# PX4FMUv2_4_6_1.net
KiCad netlist of a schematic drawn in Altium Designer
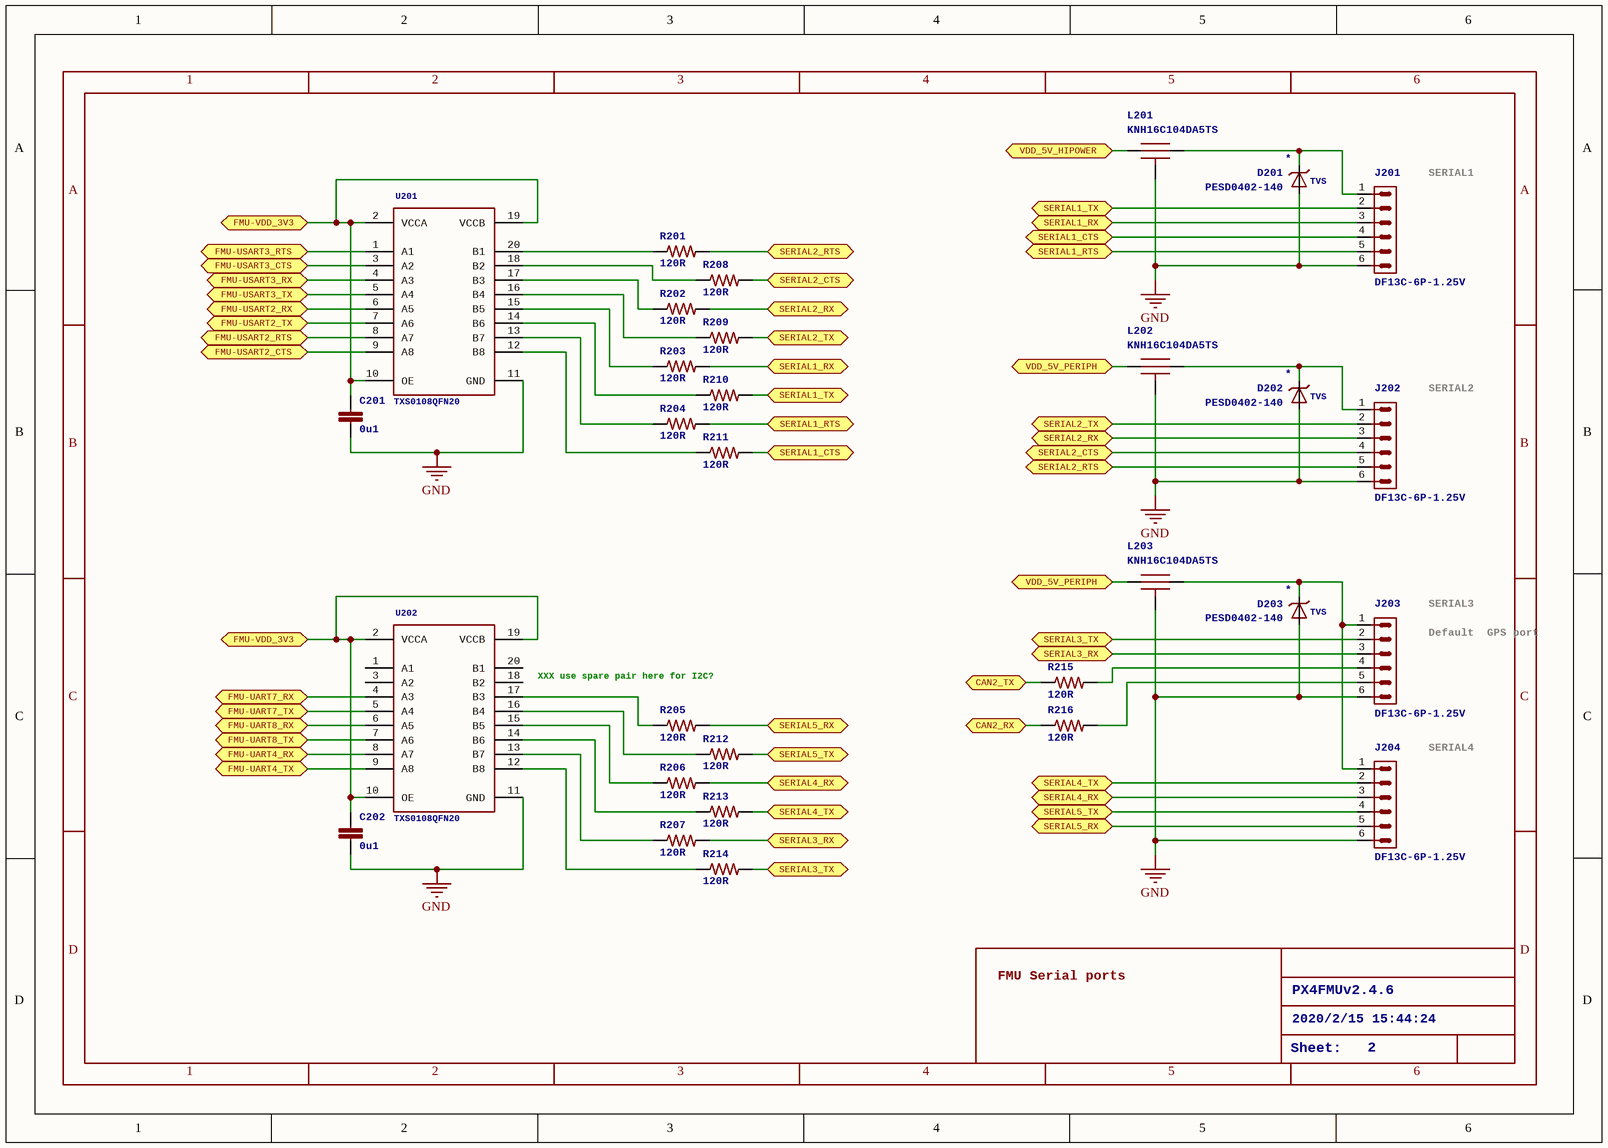
[diagram p0: PX4FMUv2.4.6_1.SchDoc]

(export (version "E")
  (design (tool "Eeschema 10.0.6"))
  (components
    (comp (ref "C201")
      (value "0u1")
      (footprint "0402-CAP")
      (description "CapacitorStandard 0603 ceramic capacitor, and 0.1\" leaded capacitor.")
      (fields (field (name "PARTNO") "CC0402ZRY5V7BB104"))
      (libsource (lib "pixhawk2") (part "CAP0402"))
    )
    (comp (ref "C202")
      (value "0u1")
      (footprint "0402-CAP")
      (description "CapacitorStandard 0603 ceramic capacitor, and 0.1\" leaded capacitor.")
      (fields (field (name "PARTNO") "CC0402ZRY5V7BB104"))
      (libsource (lib "pixhawk2") (part "CAP0402"))
    )
    (comp (ref "D201")
      (value "PESD0402-140")
      (footprint "0402-TVS")
      (fields (field (name "NAME") "*") (field (name "TVS") "TVS"))
      (libsource (lib "pixhawk2") (part "DIODE-TVS"))
    )
    (comp (ref "D202")
      (value "PESD0402-140")
      (footprint "0402-TVS")
      (fields (field (name "NAME") "*") (field (name "TVS") "TVS"))
      (libsource (lib "pixhawk2") (part "DIODE-TVS"))
    )
    (comp (ref "D203")
      (value "PESD0402-140")
      (footprint "0402-TVS")
      (fields (field (name "NAME") "*") (field (name "TVS") "TVS"))
      (libsource (lib "pixhawk2") (part "DIODE-TVS"))
    )
    (comp (ref "J201")
      (value "DF13C-6P-1.25V")
      (footprint "DF13C-6P-1.25V")
      (description "DF13-6P 1.25mm Pitch Miniature Crimping Connector.")
      (fields (field (name "PARTNO") "DF13C-6P-1.25V(20)") (field (name "LIBRARYNAME") "con-hirose-df13"))
      (libsource (lib "con-hirose-df13") (part "DF13-6P-1.25V"))
    )
    (comp (ref "J202")
      (value "DF13C-6P-1.25V")
      (footprint "DF13C-6P-1.25V")
      (description "DF13-6P 1.25mm Pitch Miniature Crimping Connector.")
      (fields (field (name "PARTNO") "DF13C-6P-1.25V(20)") (field (name "LIBRARYNAME") "con-hirose-df13"))
      (libsource (lib "con-hirose-df13") (part "DF13-6P-1.25V"))
    )
    (comp (ref "J203")
      (value "DF13C-6P-1.25V")
      (footprint "DF13C-6P-1.25V")
      (description "DF13-6P 1.25mm Pitch Miniature Crimping Connector.")
      (fields (field (name "PARTNO") "DF13C-6P-1.25V(20)") (field (name "LIBRARYNAME") "con-hirose-df13"))
      (libsource (lib "con-hirose-df13") (part "DF13-6P-1.25V"))
    )
    (comp (ref "J204")
      (value "DF13C-6P-1.25V")
      (footprint "DF13C-6P-1.25V")
      (description "DF13-6P 1.25mm Pitch Miniature Crimping Connector.")
      (fields (field (name "PARTNO") "DF13C-6P-1.25V(20)") (field (name "LIBRARYNAME") "con-hirose-df13"))
      (libsource (lib "con-hirose-df13") (part "DF13-6P-1.25V"))
    )
    (comp (ref "L201")
      (value "KNH16C104DA5TS")
      (footprint "KYOCERA-KNH16-DA")
      (description "Kyocera KNH16C104DA5TS EMI filter")
      (libsource (lib "pixhawk2") (part "KNH16C104DA5TS"))
    )
    (comp (ref "L202")
      (value "KNH16C104DA5TS")
      (footprint "KYOCERA-KNH16-DA")
      (description "Kyocera KNH16C104DA5TS EMI filter")
      (libsource (lib "pixhawk2") (part "KNH16C104DA5TS"))
    )
    (comp (ref "L203")
      (value "KNH16C104DA5TS")
      (footprint "KYOCERA-KNH16-DA")
      (description "Kyocera KNH16C104DA5TS EMI filter")
      (libsource (lib "pixhawk2") (part "KNH16C104DA5TS"))
    )
    (comp (ref "R201")
      (value "120R")
      (footprint "0402-RES")
      (fields (field (name "PARTNO") "RC0402FR-07120RL"))
      (libsource (lib "pixhawk2") (part "RESISTOR0402-RES"))
    )
    (comp (ref "R202")
      (value "120R")
      (footprint "0402-RES")
      (fields (field (name "PARTNO") "RC0402FR-07120RL"))
      (libsource (lib "pixhawk2") (part "RESISTOR0402-RES"))
    )
    (comp (ref "R203")
      (value "120R")
      (footprint "0402-RES")
      (fields (field (name "PARTNO") "RC0402FR-07120RL"))
      (libsource (lib "pixhawk2") (part "RESISTOR0402-RES"))
    )
    (comp (ref "R204")
      (value "120R")
      (footprint "0402-RES")
      (fields (field (name "PARTNO") "RC0402FR-07120RL"))
      (libsource (lib "pixhawk2") (part "RESISTOR0402-RES"))
    )
    (comp (ref "R205")
      (value "120R")
      (footprint "0402-RES")
      (fields (field (name "PARTNO") "RC0402FR-07120RL"))
      (libsource (lib "pixhawk2") (part "RESISTOR0402-RES"))
    )
    (comp (ref "R206")
      (value "120R")
      (footprint "0402-RES")
      (fields (field (name "PARTNO") "RC0402FR-07120RL"))
      (libsource (lib "pixhawk2") (part "RESISTOR0402-RES"))
    )
    (comp (ref "R207")
      (value "120R")
      (footprint "0402-RES")
      (fields (field (name "PARTNO") "RC0402FR-07120RL"))
      (libsource (lib "pixhawk2") (part "RESISTOR0402-RES"))
    )
    (comp (ref "R208")
      (value "120R")
      (footprint "0402-RES")
      (fields (field (name "PARTNO") "RC0402FR-07120RL"))
      (libsource (lib "pixhawk2") (part "RESISTOR0402-RES"))
    )
    (comp (ref "R209")
      (value "120R")
      (footprint "0402-RES")
      (fields (field (name "PARTNO") "RC0402FR-07120RL"))
      (libsource (lib "pixhawk2") (part "RESISTOR0402-RES"))
    )
    (comp (ref "R210")
      (value "120R")
      (footprint "0402-RES")
      (fields (field (name "PARTNO") "RC0402FR-07120RL"))
      (libsource (lib "pixhawk2") (part "RESISTOR0402-RES"))
    )
    (comp (ref "R211")
      (value "120R")
      (footprint "0402-RES")
      (fields (field (name "PARTNO") "RC0402FR-07120RL"))
      (libsource (lib "pixhawk2") (part "RESISTOR0402-RES"))
    )
    (comp (ref "R212")
      (value "120R")
      (footprint "0402-RES")
      (fields (field (name "PARTNO") "RC0402FR-07120RL"))
      (libsource (lib "pixhawk2") (part "RESISTOR0402-RES"))
    )
    (comp (ref "R213")
      (value "120R")
      (footprint "0402-RES")
      (fields (field (name "PARTNO") "RC0402FR-07120RL"))
      (libsource (lib "pixhawk2") (part "RESISTOR0402-RES"))
    )
    (comp (ref "R214")
      (value "120R")
      (footprint "0402-RES")
      (fields (field (name "PARTNO") "RC0402FR-07120RL"))
      (libsource (lib "pixhawk2") (part "RESISTOR0402-RES"))
    )
    (comp (ref "R215")
      (value "120R")
      (footprint "0402-RES")
      (fields (field (name "PARTNO") "RC0402FR-07120RL"))
      (libsource (lib "pixhawk2") (part "RESISTOR0402-RES"))
    )
    (comp (ref "R216")
      (value "120R")
      (footprint "0402-RES")
      (fields (field (name "PARTNO") "RC0402FR-07120RL"))
      (libsource (lib "pixhawk2") (part "RESISTOR0402-RES"))
    )
    (comp (ref "U201")
      (value "TXS0108QFN20")
      (footprint "QFN20-RGY")
      (fields (field (name "PARTNO") "TXS0108ERGYR"))
      (libsource (lib "pixhawk2") (part "TXS0108QFN20"))
    )
    (comp (ref "U202")
      (value "TXS0108QFN20")
      (footprint "QFN20-RGY")
      (fields (field (name "PARTNO") "TXS0108ERGYR"))
      (libsource (lib "pixhawk2") (part "TXS0108QFN20"))
    )
  )
  (nets
    (net (code "1") (name "/CAN2_RX") (class "Default")
      (node (ref "R216") (pin "P$1") (pinfunction "1_P$1") (pintype "passive"))
    )
    (net (code "2") (name "/CAN2_TX") (class "Default")
      (node (ref "R215") (pin "P$1") (pinfunction "1_P$1") (pintype "passive"))
    )
    (net (code "3") (name "/FMU-UART4_RX") (class "Default")
      (node (ref "U202") (pin "8") (pinfunction "A7_8") (pintype "passive"))
    )
    (net (code "4") (name "/FMU-UART4_TX") (class "Default")
      (node (ref "U202") (pin "9") (pinfunction "A8_9") (pintype "passive"))
    )
    (net (code "5") (name "/FMU-UART7_RX") (class "Default")
      (node (ref "U202") (pin "4") (pinfunction "A3_4") (pintype "passive"))
    )
    (net (code "6") (name "/FMU-UART7_TX") (class "Default")
      (node (ref "U202") (pin "5") (pinfunction "A4_5") (pintype "passive"))
    )
    (net (code "7") (name "/FMU-UART8_RX") (class "Default")
      (node (ref "U202") (pin "6") (pinfunction "A5_6") (pintype "passive"))
    )
    (net (code "8") (name "/FMU-UART8_TX") (class "Default")
      (node (ref "U202") (pin "7") (pinfunction "A6_7") (pintype "passive"))
    )
    (net (code "9") (name "/FMU-USART2_CTS") (class "Default")
      (node (ref "U201") (pin "9") (pinfunction "A8_9") (pintype "passive"))
    )
    (net (code "10") (name "/FMU-USART2_RTS") (class "Default")
      (node (ref "U201") (pin "8") (pinfunction "A7_8") (pintype "passive"))
    )
    (net (code "11") (name "/FMU-USART2_RX") (class "Default")
      (node (ref "U201") (pin "6") (pinfunction "A5_6") (pintype "passive"))
    )
    (net (code "12") (name "/FMU-USART2_TX") (class "Default")
      (node (ref "U201") (pin "7") (pinfunction "A6_7") (pintype "passive"))
    )
    (net (code "13") (name "/FMU-USART3_CTS") (class "Default")
      (node (ref "U201") (pin "3") (pinfunction "A2_3") (pintype "passive"))
    )
    (net (code "14") (name "/FMU-USART3_RTS") (class "Default")
      (node (ref "U201") (pin "1") (pinfunction "A1_1") (pintype "passive"))
    )
    (net (code "15") (name "/FMU-USART3_RX") (class "Default")
      (node (ref "U201") (pin "4") (pinfunction "A3_4") (pintype "passive"))
    )
    (net (code "16") (name "/FMU-USART3_TX") (class "Default")
      (node (ref "U201") (pin "5") (pinfunction "A4_5") (pintype "passive"))
    )
    (net (code "17") (name "/FMU-VDD_3V3") (class "Default")
      (node (ref "C201") (pin "P$1") (pinfunction "1_P$1") (pintype "passive"))
      (node (ref "C202") (pin "P$1") (pinfunction "1_P$1") (pintype "passive"))
      (node (ref "U201") (pin "10") (pinfunction "OE_10") (pintype "passive"))
      (node (ref "U201") (pin "19") (pinfunction "VCCB_19") (pintype "passive"))
      (node (ref "U201") (pin "2") (pinfunction "VCCA_2") (pintype "passive"))
      (node (ref "U202") (pin "10") (pinfunction "OE_10") (pintype "passive"))
      (node (ref "U202") (pin "19") (pinfunction "VCCB_19") (pintype "passive"))
      (node (ref "U202") (pin "2") (pinfunction "VCCA_2") (pintype "passive"))
    )
    (net (code "18") (name "/SERIAL1_CTS") (class "Default")
      (node (ref "J201") (pin "4") (pinfunction "4_4") (pintype "passive"))
      (node (ref "R211") (pin "P$2") (pinfunction "2_P$2") (pintype "passive"))
    )
    (net (code "19") (name "/SERIAL1_RTS") (class "Default")
      (node (ref "J201") (pin "5") (pinfunction "5_5") (pintype "passive"))
      (node (ref "R204") (pin "P$2") (pinfunction "2_P$2") (pintype "passive"))
    )
    (net (code "20") (name "/SERIAL1_RX") (class "Default")
      (node (ref "J201") (pin "3") (pinfunction "3_3") (pintype "passive"))
      (node (ref "R203") (pin "P$2") (pinfunction "2_P$2") (pintype "passive"))
    )
    (net (code "21") (name "/SERIAL1_TX") (class "Default")
      (node (ref "J201") (pin "2") (pinfunction "2_2") (pintype "passive"))
      (node (ref "R210") (pin "P$2") (pinfunction "2_P$2") (pintype "passive"))
    )
    (net (code "22") (name "/SERIAL2_CTS") (class "Default")
      (node (ref "J202") (pin "4") (pinfunction "4_4") (pintype "passive"))
      (node (ref "R208") (pin "P$2") (pinfunction "2_P$2") (pintype "passive"))
    )
    (net (code "23") (name "/SERIAL2_RTS") (class "Default")
      (node (ref "J202") (pin "5") (pinfunction "5_5") (pintype "passive"))
      (node (ref "R201") (pin "P$2") (pinfunction "2_P$2") (pintype "passive"))
    )
    (net (code "24") (name "/SERIAL2_RX") (class "Default")
      (node (ref "J202") (pin "3") (pinfunction "3_3") (pintype "passive"))
      (node (ref "R202") (pin "P$2") (pinfunction "2_P$2") (pintype "passive"))
    )
    (net (code "25") (name "/SERIAL2_TX") (class "Default")
      (node (ref "J202") (pin "2") (pinfunction "2_2") (pintype "passive"))
      (node (ref "R209") (pin "P$2") (pinfunction "2_P$2") (pintype "passive"))
    )
    (net (code "26") (name "/SERIAL3_RX") (class "Default")
      (node (ref "J203") (pin "3") (pinfunction "3_3") (pintype "passive"))
      (node (ref "R207") (pin "P$2") (pinfunction "2_P$2") (pintype "passive"))
    )
    (net (code "27") (name "/SERIAL3_TX") (class "Default")
      (node (ref "J203") (pin "2") (pinfunction "2_2") (pintype "passive"))
      (node (ref "R214") (pin "P$2") (pinfunction "2_P$2") (pintype "passive"))
    )
    (net (code "28") (name "/SERIAL4_RX") (class "Default")
      (node (ref "J204") (pin "3") (pinfunction "3_3") (pintype "passive"))
      (node (ref "R206") (pin "P$2") (pinfunction "2_P$2") (pintype "passive"))
    )
    (net (code "29") (name "/SERIAL4_TX") (class "Default")
      (node (ref "J204") (pin "2") (pinfunction "2_2") (pintype "passive"))
      (node (ref "R213") (pin "P$2") (pinfunction "2_P$2") (pintype "passive"))
    )
    (net (code "30") (name "/SERIAL5_RX") (class "Default")
      (node (ref "J204") (pin "5") (pinfunction "5_5") (pintype "passive"))
      (node (ref "R205") (pin "P$2") (pinfunction "2_P$2") (pintype "passive"))
    )
    (net (code "31") (name "/SERIAL5_TX") (class "Default")
      (node (ref "J204") (pin "4") (pinfunction "4_4") (pintype "passive"))
      (node (ref "R212") (pin "P$2") (pinfunction "2_P$2") (pintype "passive"))
    )
    (net (code "32") (name "/VDD_5V_HIPOWER") (class "Default")
      (node (ref "L201") (pin "P$1") (pinfunction "P$1_P$1") (pintype "passive"))
    )
    (net (code "33") (name "/VDD_5V_PERIPH") (class "Default")
      (node (ref "L202") (pin "P$1") (pinfunction "P$1_P$1") (pintype "passive"))
      (node (ref "L203") (pin "P$1") (pinfunction "P$1_P$1") (pintype "passive"))
    )
    (net (code "34") (name "GND") (class "Default")
      (node (ref "C201") (pin "P$2") (pinfunction "2_P$2") (pintype "passive"))
      (node (ref "C202") (pin "P$2") (pinfunction "2_P$2") (pintype "passive"))
      (node (ref "D201") (pin "A") (pinfunction "A_A") (pintype "passive"))
      (node (ref "D202") (pin "A") (pinfunction "A_A") (pintype "passive"))
      (node (ref "D203") (pin "A") (pinfunction "A_A") (pintype "passive"))
      (node (ref "J201") (pin "6") (pinfunction "6_6") (pintype "passive"))
      (node (ref "J202") (pin "6") (pinfunction "6_6") (pintype "passive"))
      (node (ref "J203") (pin "6") (pinfunction "6_6") (pintype "passive"))
      (node (ref "J204") (pin "6") (pinfunction "6_6") (pintype "passive"))
      (node (ref "L201") (pin "P$3_P$4_P$5") (pinfunction "P$3_P$3_P$4_P$5") (pintype "passive"))
      (node (ref "L202") (pin "P$3_P$4_P$5") (pinfunction "P$3_P$3_P$4_P$5") (pintype "passive"))
      (node (ref "L203") (pin "P$3_P$4_P$5") (pinfunction "P$3_P$3_P$4_P$5") (pintype "passive"))
      (node (ref "U201") (pin "11") (pinfunction "GND_11") (pintype "open_emitter"))
      (node (ref "U202") (pin "11") (pinfunction "GND_11") (pintype "open_emitter"))
    )
    (net (code "35") (name "Net-(D201-PadC)") (class "Default")
      (node (ref "D201") (pin "C") (pinfunction "C_C") (pintype "passive"))
      (node (ref "J201") (pin "1") (pinfunction "1_1") (pintype "passive"))
      (node (ref "L201") (pin "P$2") (pinfunction "P$2_P$2") (pintype "passive"))
    )
    (net (code "36") (name "Net-(D202-PadC)") (class "Default")
      (node (ref "D202") (pin "C") (pinfunction "C_C") (pintype "passive"))
      (node (ref "J202") (pin "1") (pinfunction "1_1") (pintype "passive"))
      (node (ref "L202") (pin "P$2") (pinfunction "P$2_P$2") (pintype "passive"))
    )
    (net (code "37") (name "Net-(D203-PadC)") (class "Default")
      (node (ref "D203") (pin "C") (pinfunction "C_C") (pintype "passive"))
      (node (ref "J203") (pin "1") (pinfunction "1_1") (pintype "passive"))
      (node (ref "J204") (pin "1") (pinfunction "1_1") (pintype "passive"))
      (node (ref "L203") (pin "P$2") (pinfunction "P$2_P$2") (pintype "passive"))
    )
    (net (code "38") (name "Net-(R201-1)") (class "Default")
      (node (ref "R201") (pin "P$1") (pinfunction "1_P$1") (pintype "passive"))
      (node (ref "U201") (pin "20") (pinfunction "B1_20") (pintype "passive"))
    )
    (net (code "39") (name "Net-(R202-1)") (class "Default")
      (node (ref "R202") (pin "P$1") (pinfunction "1_P$1") (pintype "passive"))
      (node (ref "U201") (pin "17") (pinfunction "B3_17") (pintype "passive"))
    )
    (net (code "40") (name "Net-(R203-1)") (class "Default")
      (node (ref "R203") (pin "P$1") (pinfunction "1_P$1") (pintype "passive"))
      (node (ref "U201") (pin "15") (pinfunction "B5_15") (pintype "passive"))
    )
    (net (code "41") (name "Net-(R204-1)") (class "Default")
      (node (ref "R204") (pin "P$1") (pinfunction "1_P$1") (pintype "passive"))
      (node (ref "U201") (pin "13") (pinfunction "B7_13") (pintype "passive"))
    )
    (net (code "42") (name "Net-(R205-1)") (class "Default")
      (node (ref "R205") (pin "P$1") (pinfunction "1_P$1") (pintype "passive"))
      (node (ref "U202") (pin "17") (pinfunction "B3_17") (pintype "passive"))
    )
    (net (code "43") (name "Net-(R206-1)") (class "Default")
      (node (ref "R206") (pin "P$1") (pinfunction "1_P$1") (pintype "passive"))
      (node (ref "U202") (pin "15") (pinfunction "B5_15") (pintype "passive"))
    )
    (net (code "44") (name "Net-(R207-1)") (class "Default")
      (node (ref "R207") (pin "P$1") (pinfunction "1_P$1") (pintype "passive"))
      (node (ref "U202") (pin "13") (pinfunction "B7_13") (pintype "passive"))
    )
    (net (code "45") (name "Net-(R208-1)") (class "Default")
      (node (ref "R208") (pin "P$1") (pinfunction "1_P$1") (pintype "passive"))
      (node (ref "U201") (pin "18") (pinfunction "B2_18") (pintype "passive"))
    )
    (net (code "46") (name "Net-(R209-1)") (class "Default")
      (node (ref "R209") (pin "P$1") (pinfunction "1_P$1") (pintype "passive"))
      (node (ref "U201") (pin "16") (pinfunction "B4_16") (pintype "passive"))
    )
    (net (code "47") (name "Net-(R210-1)") (class "Default")
      (node (ref "R210") (pin "P$1") (pinfunction "1_P$1") (pintype "passive"))
      (node (ref "U201") (pin "14") (pinfunction "B6_14") (pintype "passive"))
    )
    (net (code "48") (name "Net-(R211-1)") (class "Default")
      (node (ref "R211") (pin "P$1") (pinfunction "1_P$1") (pintype "passive"))
      (node (ref "U201") (pin "12") (pinfunction "B8_12") (pintype "passive"))
    )
    (net (code "49") (name "Net-(R212-1)") (class "Default")
      (node (ref "R212") (pin "P$1") (pinfunction "1_P$1") (pintype "passive"))
      (node (ref "U202") (pin "16") (pinfunction "B4_16") (pintype "passive"))
    )
    (net (code "50") (name "Net-(R213-1)") (class "Default")
      (node (ref "R213") (pin "P$1") (pinfunction "1_P$1") (pintype "passive"))
      (node (ref "U202") (pin "14") (pinfunction "B6_14") (pintype "passive"))
    )
    (net (code "51") (name "Net-(R214-1)") (class "Default")
      (node (ref "R214") (pin "P$1") (pinfunction "1_P$1") (pintype "passive"))
      (node (ref "U202") (pin "12") (pinfunction "B8_12") (pintype "passive"))
    )
    (net (code "52") (name "Net-(R215-2)") (class "Default")
      (node (ref "J203") (pin "4") (pinfunction "4_4") (pintype "passive"))
      (node (ref "R215") (pin "P$2") (pinfunction "2_P$2") (pintype "passive"))
    )
    (net (code "53") (name "Net-(R216-2)") (class "Default")
      (node (ref "J203") (pin "5") (pinfunction "5_5") (pintype "passive"))
      (node (ref "R216") (pin "P$2") (pinfunction "2_P$2") (pintype "passive"))
    )
    (net (code "54") (name "unconnected-(U202-A1-Pad1)") (class "Default")
      (node (ref "U202") (pin "1") (pinfunction "A1_1") (pintype "passive"))
    )
    (net (code "55") (name "unconnected-(U202-A2-Pad3)") (class "Default")
      (node (ref "U202") (pin "3") (pinfunction "A2_3") (pintype "passive"))
    )
    (net (code "56") (name "unconnected-(U202-B1-Pad20)") (class "Default")
      (node (ref "U202") (pin "20") (pinfunction "B1_20") (pintype "passive"))
    )
    (net (code "57") (name "unconnected-(U202-B2-Pad18)") (class "Default")
      (node (ref "U202") (pin "18") (pinfunction "B2_18") (pintype "passive"))
    )
  )
)
